# wzy_SCH1.net
KiCad netlist of a schematic drawn in Altium Designer
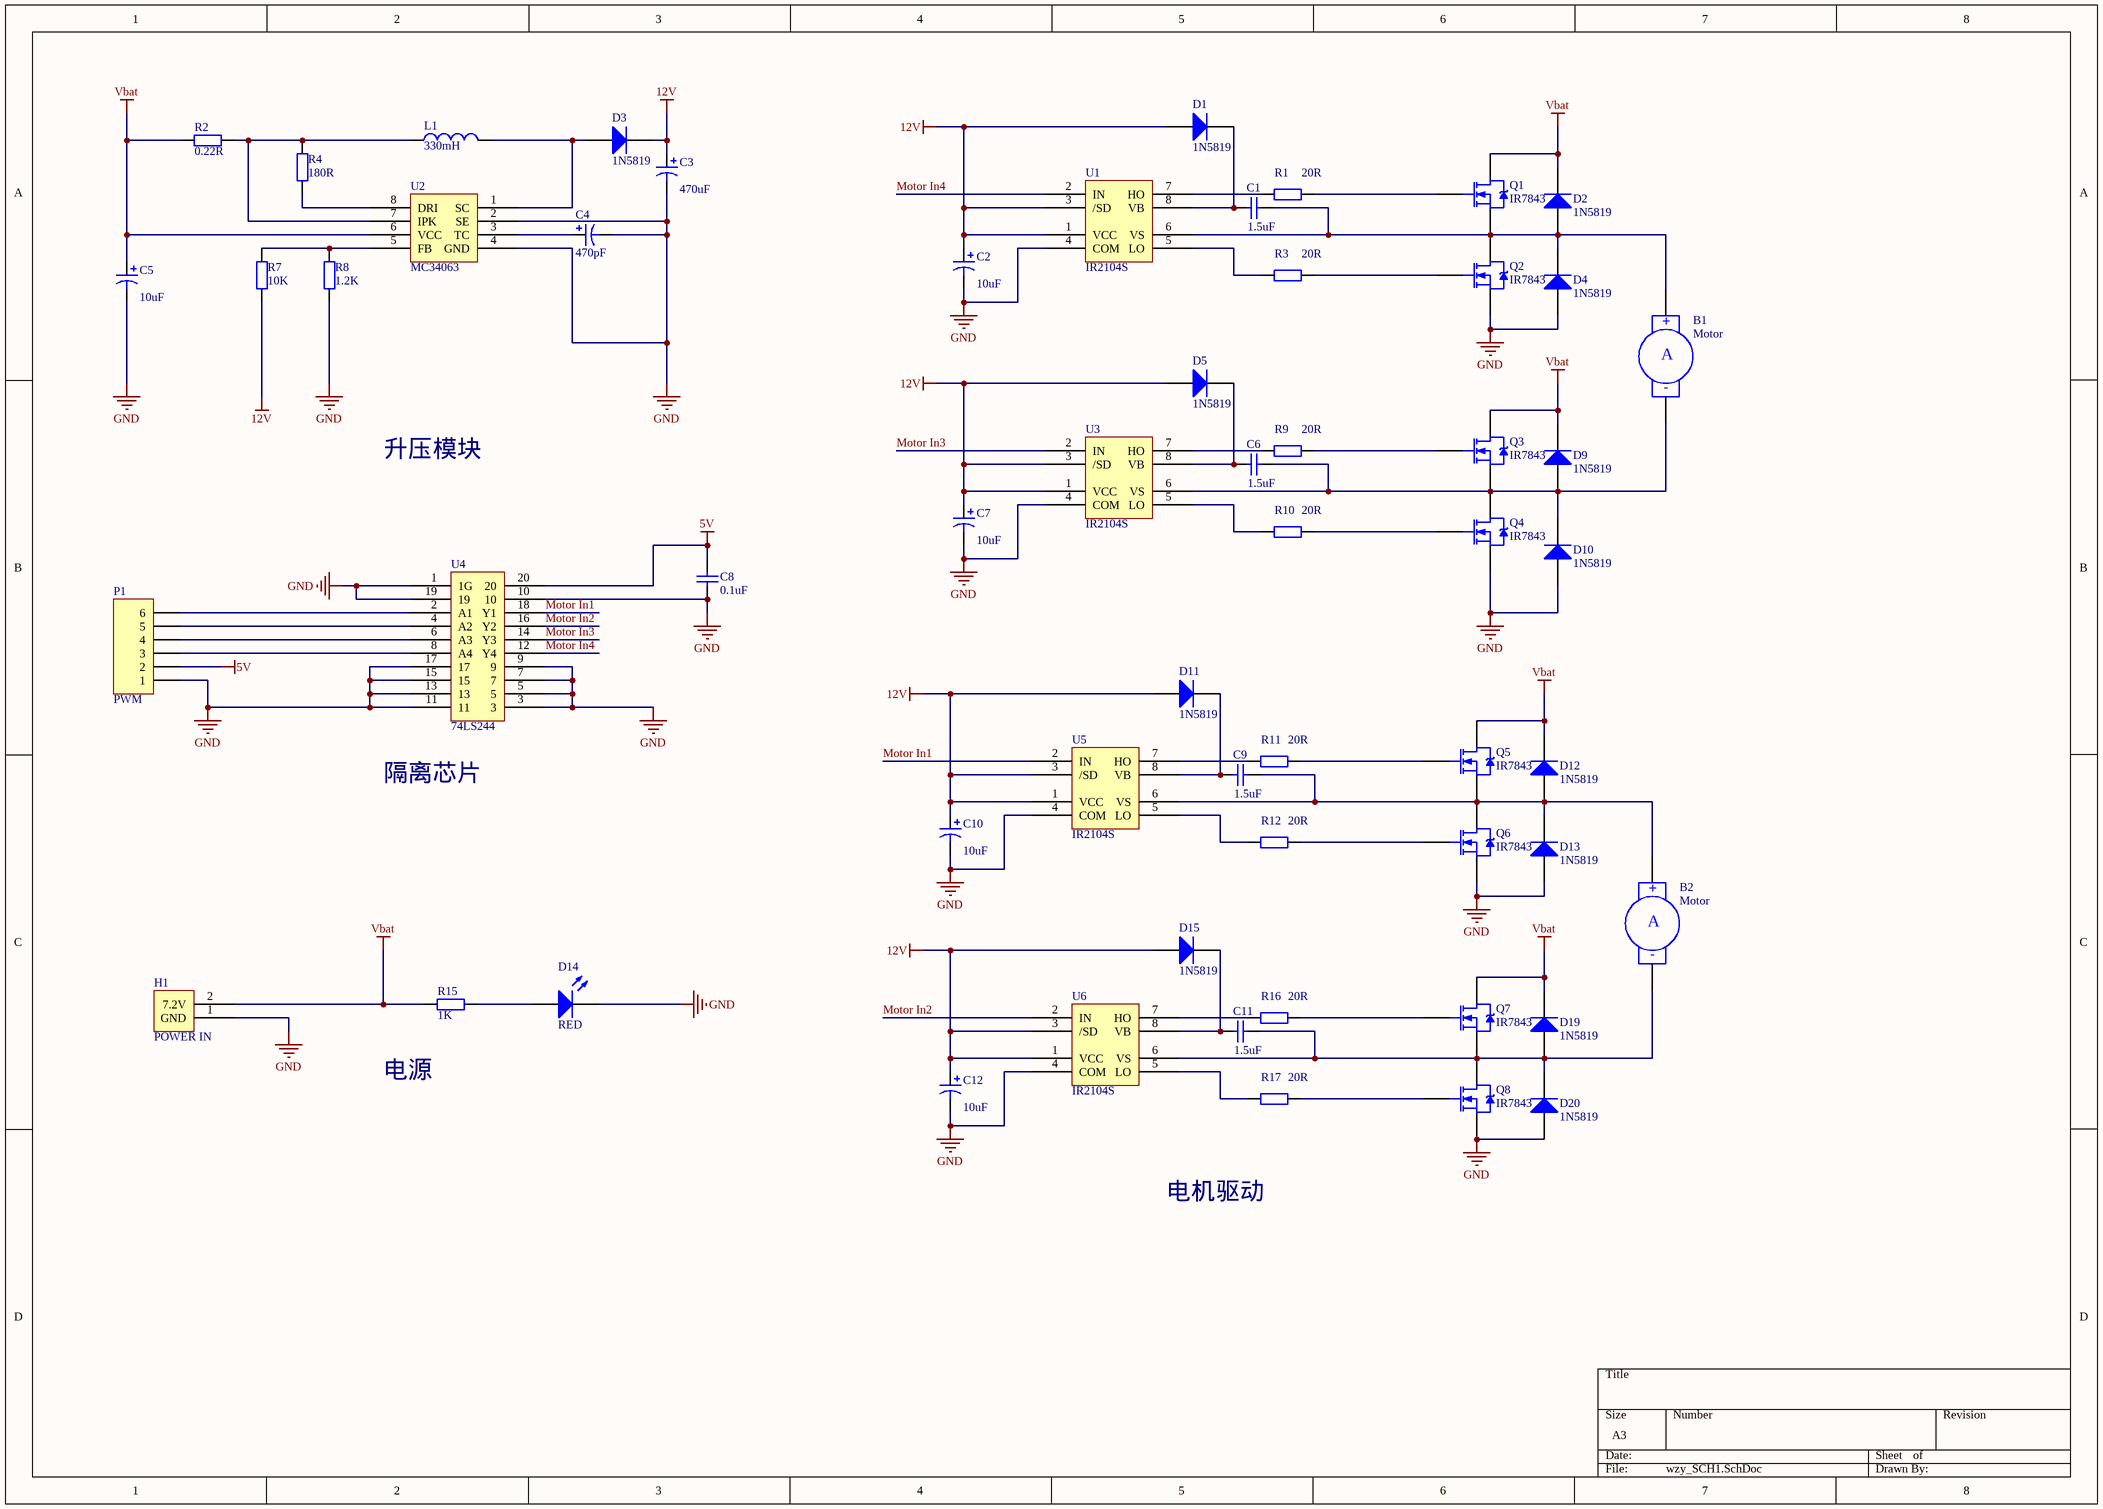
[diagram p0: wzy_SCH1.SchDoc]

(export (version "E")
  (design (tool "Eeschema 10.0.6"))
  (components
    (comp (ref "B1")
      (value "Motor")
      (footprint "KF301-2P")
      (description "Servo Motor")
      (fields (field (name "PUBLISHER") "Altium Limited"))
      (libsource (lib "Miscellaneous Devices") (part "Motor Servo"))
    )
    (comp (ref "B2")
      (value "Motor")
      (footprint "KF301-2P")
      (description "Servo Motor")
      (fields (field (name "PUBLISHER") "Altium Limited"))
      (libsource (lib "Miscellaneous Devices") (part "Motor Servo"))
    )
    (comp (ref "C1")
      (value "1.5uF")
      (footprint "0805(2012)")
      (description "Capacitor")
      (fields (field (name "Comment") "Cap") (field (name "PUBLISHER") "Altium Limited"))
      (libsource (lib "Miscellaneous Devices") (part "Cap"))
    )
    (comp (ref "C2")
      (value "10uF")
      (footprint "SOD-323(0805)")
      (description "Polarized Capacitor (Radial)")
      (fields (field (name "Comment") "Cap Pol1") (field (name "PUBLISHER") "Altium Limited"))
      (libsource (lib "Miscellaneous Devices") (part "Cap Pol1"))
    )
    (comp (ref "C3")
      (value "470uF")
      (footprint "RB5-10.5")
      (description "Polarized Capacitor (Radial)")
      (fields (field (name "Comment") "Cap Pol1") (field (name "PUBLISHER") "Altium Limited"))
      (libsource (lib "Miscellaneous Devices") (part "Cap Pol1"))
    )
    (comp (ref "C4")
      (value "470pF")
      (footprint "SOD-323(0805)")
      (description "Polarized Capacitor (Radial)")
      (fields (field (name "Comment") "Cap Pol1") (field (name "PUBLISHER") "Altium Limited"))
      (libsource (lib "Miscellaneous Devices") (part "Cap Pol1"))
    )
    (comp (ref "C5")
      (value "10uF")
      (footprint "SOD-323(0805)")
      (description "Polarized Capacitor (Radial)")
      (fields (field (name "Comment") "Cap Pol1") (field (name "PUBLISHER") "Altium Limited"))
      (libsource (lib "Miscellaneous Devices") (part "Cap Pol1"))
    )
    (comp (ref "C6")
      (value "1.5uF")
      (footprint "0805(2012)")
      (description "Capacitor")
      (fields (field (name "Comment") "Cap") (field (name "PUBLISHER") "Altium Limited"))
      (libsource (lib "Miscellaneous Devices") (part "Cap"))
    )
    (comp (ref "C7")
      (value "10uF")
      (footprint "SOD-323(0805)")
      (description "Polarized Capacitor (Radial)")
      (fields (field (name "Comment") "Cap Pol1") (field (name "PUBLISHER") "Altium Limited"))
      (libsource (lib "Miscellaneous Devices") (part "Cap Pol1"))
    )
    (comp (ref "C8")
      (value "0.1uF")
      (footprint "0805(2012)")
      (description "Capacitor")
      (fields (field (name "Comment") "Cap") (field (name "PUBLISHER") "Altium Limited"))
      (libsource (lib "LY") (part "Cap"))
    )
    (comp (ref "C9")
      (value "1.5uF")
      (footprint "0805(2012)")
      (description "Capacitor")
      (fields (field (name "Comment") "Cap") (field (name "PUBLISHER") "Altium Limited"))
      (libsource (lib "Miscellaneous Devices") (part "Cap"))
    )
    (comp (ref "C10")
      (value "10uF")
      (footprint "SOD-323(0805)")
      (description "Polarized Capacitor (Radial)")
      (fields (field (name "Comment") "Cap Pol1") (field (name "PUBLISHER") "Altium Limited"))
      (libsource (lib "Miscellaneous Devices") (part "Cap Pol1"))
    )
    (comp (ref "C11")
      (value "1.5uF")
      (footprint "0805(2012)")
      (description "Capacitor")
      (fields (field (name "Comment") "Cap") (field (name "PUBLISHER") "Altium Limited"))
      (libsource (lib "Miscellaneous Devices") (part "Cap"))
    )
    (comp (ref "C12")
      (value "10uF")
      (footprint "SOD-323(0805)")
      (description "Polarized Capacitor (Radial)")
      (fields (field (name "Comment") "Cap Pol1") (field (name "PUBLISHER") "Altium Limited"))
      (libsource (lib "Miscellaneous Devices") (part "Cap Pol1"))
    )
    (comp (ref "D1")
      (value "1N5819")
      (footprint "0805(2012)")
      (description "Silicon Epitaxial Planar Diode for Various Detector, Modulator, Demodulator")
      (fields (field (name "PUBLISHER") "Altium Limited"))
      (libsource (lib "Renesas Diode") (part "1N4148"))
    )
    (comp (ref "D2")
      (value "1N5819")
      (footprint "0805(2012)")
      (description "Silicon Epitaxial Planar Diode for Various Detector, Modulator, Demodulator")
      (fields (field (name "PUBLISHER") "Altium Limited"))
      (libsource (lib "Renesas Diode") (part "1N4148"))
    )
    (comp (ref "D3")
      (value "1N5819")
      (footprint "0805(2012)")
      (description "Silicon Epitaxial Planar Diode for Various Detector, Modulator, Demodulator")
      (fields (field (name "PUBLISHER") "Altium Limited"))
      (libsource (lib "Renesas Diode") (part "1N4148"))
    )
    (comp (ref "D4")
      (value "1N5819")
      (footprint "0805(2012)")
      (description "Silicon Epitaxial Planar Diode for Various Detector, Modulator, Demodulator")
      (fields (field (name "PUBLISHER") "Altium Limited"))
      (libsource (lib "Renesas Diode") (part "1N4148"))
    )
    (comp (ref "D5")
      (value "1N5819")
      (footprint "0805(2012)")
      (description "Silicon Epitaxial Planar Diode for Various Detector, Modulator, Demodulator")
      (fields (field (name "PUBLISHER") "Altium Limited"))
      (libsource (lib "Renesas Diode") (part "1N4148"))
    )
    (comp (ref "D9")
      (value "1N5819")
      (footprint "0805(2012)")
      (description "Silicon Epitaxial Planar Diode for Various Detector, Modulator, Demodulator")
      (fields (field (name "PUBLISHER") "Altium Limited"))
      (libsource (lib "Renesas Diode") (part "1N4148"))
    )
    (comp (ref "D10")
      (value "1N5819")
      (footprint "0805(2012)")
      (description "Silicon Epitaxial Planar Diode for Various Detector, Modulator, Demodulator")
      (fields (field (name "PUBLISHER") "Altium Limited"))
      (libsource (lib "Renesas Diode") (part "1N4148"))
    )
    (comp (ref "D11")
      (value "1N5819")
      (footprint "0805(2012)")
      (description "Silicon Epitaxial Planar Diode for Various Detector, Modulator, Demodulator")
      (fields (field (name "PUBLISHER") "Altium Limited"))
      (libsource (lib "Renesas Diode") (part "1N4148"))
    )
    (comp (ref "D12")
      (value "1N5819")
      (footprint "0805(2012)")
      (description "Silicon Epitaxial Planar Diode for Various Detector, Modulator, Demodulator")
      (fields (field (name "PUBLISHER") "Altium Limited"))
      (libsource (lib "Renesas Diode") (part "1N4148"))
    )
    (comp (ref "D13")
      (value "1N5819")
      (footprint "0805(2012)")
      (description "Silicon Epitaxial Planar Diode for Various Detector, Modulator, Demodulator")
      (fields (field (name "PUBLISHER") "Altium Limited"))
      (libsource (lib "Renesas Diode") (part "1N4148"))
    )
    (comp (ref "D14")
      (value "RED")
      (footprint "0805LED")
      (description "Typical RED, GREEN, YELLOW, AMBER GaAs LED")
      (fields (field (name "PUBLISHER") "Altium Limited"))
      (libsource (lib "LY") (part "LED2"))
    )
    (comp (ref "D15")
      (value "1N5819")
      (footprint "0805(2012)")
      (description "Silicon Epitaxial Planar Diode for Various Detector, Modulator, Demodulator")
      (fields (field (name "PUBLISHER") "Altium Limited"))
      (libsource (lib "Renesas Diode") (part "1N4148"))
    )
    (comp (ref "D19")
      (value "1N5819")
      (footprint "0805(2012)")
      (description "Silicon Epitaxial Planar Diode for Various Detector, Modulator, Demodulator")
      (fields (field (name "PUBLISHER") "Altium Limited"))
      (libsource (lib "Renesas Diode") (part "1N4148"))
    )
    (comp (ref "D20")
      (value "1N5819")
      (footprint "0805(2012)")
      (description "Silicon Epitaxial Planar Diode for Various Detector, Modulator, Demodulator")
      (fields (field (name "PUBLISHER") "Altium Limited"))
      (libsource (lib "Renesas Diode") (part "1N4148"))
    )
    (comp (ref "H1")
      (value "POWER IN")
      (footprint "KF301-2P")
      (libsource (lib "MOS motor") (part "POWER IN"))
    )
    (comp (ref "L1")
      (value "330mH")
      (footprint "电感10*12")
      (description "Inductor")
      (fields (field (name "PUBLISHER") "Altium Limited"))
      (libsource (lib "Miscellaneous Devices") (part "Inductor"))
    )
    (comp (ref "P1")
      (value "PWM")
      (footprint "HDR1X6")
      (description "Header, 6-Pin")
      (fields (field (name "PUBLISHER") "Altium Limited"))
      (libsource (lib "Miscellaneous Connectors") (part "Header 6"))
    )
    (comp (ref "Q1")
      (value "IR7843")
      (footprint "LR7843")
      (description "N-Channel Power MOSFET")
      (fields (field (name "PUBLISHER") "Altium Limited"))
      (libsource (lib "PowerIn") (part "IR7843"))
    )
    (comp (ref "Q2")
      (value "IR7843")
      (footprint "LR7843")
      (description "N-Channel Power MOSFET")
      (fields (field (name "PUBLISHER") "Altium Limited"))
      (libsource (lib "PowerIn") (part "IR7843"))
    )
    (comp (ref "Q3")
      (value "IR7843")
      (footprint "LR7843")
      (description "N-Channel Power MOSFET")
      (fields (field (name "PUBLISHER") "Altium Limited"))
      (libsource (lib "PowerIn") (part "IR7843"))
    )
    (comp (ref "Q4")
      (value "IR7843")
      (footprint "LR7843")
      (description "N-Channel Power MOSFET")
      (fields (field (name "PUBLISHER") "Altium Limited"))
      (libsource (lib "PowerIn") (part "IR7843"))
    )
    (comp (ref "Q5")
      (value "IR7843")
      (footprint "LR7843")
      (description "N-Channel Power MOSFET")
      (fields (field (name "PUBLISHER") "Altium Limited"))
      (libsource (lib "PowerIn") (part "IR7843"))
    )
    (comp (ref "Q6")
      (value "IR7843")
      (footprint "LR7843")
      (description "N-Channel Power MOSFET")
      (fields (field (name "PUBLISHER") "Altium Limited"))
      (libsource (lib "PowerIn") (part "IR7843"))
    )
    (comp (ref "Q7")
      (value "IR7843")
      (footprint "LR7843")
      (description "N-Channel Power MOSFET")
      (fields (field (name "PUBLISHER") "Altium Limited"))
      (libsource (lib "PowerIn") (part "IR7843"))
    )
    (comp (ref "Q8")
      (value "IR7843")
      (footprint "LR7843")
      (description "N-Channel Power MOSFET")
      (fields (field (name "PUBLISHER") "Altium Limited"))
      (libsource (lib "PowerIn") (part "IR7843"))
    )
    (comp (ref "R1")
      (value "20R")
      (footprint "0805(2012)")
      (description "Resistor")
      (fields (field (name "Comment") "Res2") (field (name "PUBLISHER") "Altium Limited"))
      (libsource (lib "altium-import") (part "root_0_Res2_"))
    )
    (comp (ref "R2")
      (value "0.22R")
      (footprint "1206(3216)")
      (description "Resistor")
      (fields (field (name "Comment") "Res2") (field (name "PUBLISHER") "Altium Limited"))
      (libsource (lib "altium-import") (part "root_2_Res2_"))
    )
    (comp (ref "R3")
      (value "20R")
      (footprint "0805(2012)")
      (description "Resistor")
      (fields (field (name "Comment") "Res2") (field (name "PUBLISHER") "Altium Limited"))
      (libsource (lib "altium-import") (part "root_0_Res2_"))
    )
    (comp (ref "R4")
      (value "180R")
      (footprint "0805(2012)")
      (description "Resistor")
      (fields (field (name "Comment") "Res2") (field (name "PUBLISHER") "Altium Limited"))
      (libsource (lib "LY") (part "Res2"))
    )
    (comp (ref "R7")
      (value "10K")
      (footprint "0805(2012)")
      (description "Resistor")
      (fields (field (name "Comment") "Res2") (field (name "PUBLISHER") "Altium Limited"))
      (libsource (lib "LY") (part "Res2"))
    )
    (comp (ref "R8")
      (value "1.2K")
      (footprint "0805(2012)")
      (description "Resistor")
      (fields (field (name "Comment") "Res2") (field (name "PUBLISHER") "Altium Limited"))
      (libsource (lib "LY") (part "Res2"))
    )
    (comp (ref "R9")
      (value "20R")
      (footprint "0805(2012)")
      (description "Resistor")
      (fields (field (name "Comment") "Res2") (field (name "PUBLISHER") "Altium Limited"))
      (libsource (lib "altium-import") (part "root_0_Res2_"))
    )
    (comp (ref "R10")
      (value "20R")
      (footprint "0805(2012)")
      (description "Resistor")
      (fields (field (name "Comment") "Res2") (field (name "PUBLISHER") "Altium Limited"))
      (libsource (lib "altium-import") (part "root_0_Res2_"))
    )
    (comp (ref "R11")
      (value "20R")
      (footprint "0805(2012)")
      (description "Resistor")
      (fields (field (name "Comment") "Res2") (field (name "PUBLISHER") "Altium Limited"))
      (libsource (lib "altium-import") (part "root_0_Res2_"))
    )
    (comp (ref "R12")
      (value "20R")
      (footprint "0805(2012)")
      (description "Resistor")
      (fields (field (name "Comment") "Res2") (field (name "PUBLISHER") "Altium Limited"))
      (libsource (lib "altium-import") (part "root_0_Res2_"))
    )
    (comp (ref "R15")
      (value "1K")
      (footprint "0805(2012)")
      (description "Resistor")
      (fields (field (name "Comment") "Res2") (field (name "PUBLISHER") "Altium Limited"))
      (libsource (lib "") (part "Res2_1"))
    )
    (comp (ref "R16")
      (value "20R")
      (footprint "0805(2012)")
      (description "Resistor")
      (fields (field (name "Comment") "Res2") (field (name "PUBLISHER") "Altium Limited"))
      (libsource (lib "altium-import") (part "root_0_Res2_"))
    )
    (comp (ref "R17")
      (value "20R")
      (footprint "0805(2012)")
      (description "Resistor")
      (fields (field (name "Comment") "Res2") (field (name "PUBLISHER") "Altium Limited"))
      (libsource (lib "altium-import") (part "root_0_Res2_"))
    )
    (comp (ref "U1") (value "IR2104S") (footprint "IR2104S") (libsource (lib "LY") (part "IR2104S")))
    (comp (ref "U2") (value "MC34063") (footprint "MC34063") (libsource (lib "LY") (part "MC34063")))
    (comp (ref "U3") (value "IR2104S") (footprint "IR2104S") (libsource (lib "LY") (part "IR2104S")))
    (comp (ref "U4") (value "74LS244") (footprint "74ls244DA") (libsource (lib "LY") (part "74LS244")))
    (comp (ref "U5") (value "IR2104S") (footprint "IR2104S") (libsource (lib "LY") (part "IR2104S")))
    (comp (ref "U6") (value "IR2104S") (footprint "IR2104S") (libsource (lib "LY") (part "IR2104S")))
  )
  (nets
    (net (code "1") (name "/Motor In1") (class "Default")
      (node (ref "U4") (pin "18") (pinfunction "Y1_18") (pintype "passive"))
      (node (ref "U5") (pin "2") (pinfunction "IN_2") (pintype "passive"))
    )
    (net (code "2") (name "/Motor In2") (class "Default")
      (node (ref "U4") (pin "16") (pinfunction "Y2_16") (pintype "passive"))
      (node (ref "U6") (pin "2") (pinfunction "IN_2") (pintype "passive"))
    )
    (net (code "3") (name "/Motor In3") (class "Default")
      (node (ref "U3") (pin "2") (pinfunction "IN_2") (pintype "passive"))
      (node (ref "U4") (pin "14") (pinfunction "Y3_14") (pintype "passive"))
    )
    (net (code "4") (name "/Motor In4") (class "Default")
      (node (ref "U1") (pin "2") (pinfunction "IN_2") (pintype "passive"))
      (node (ref "U4") (pin "12") (pinfunction "Y4_12") (pintype "passive"))
    )
    (net (code "5") (name "5V") (class "Default")
      (node (ref "C8") (pin "2") (pinfunction "2_2") (pintype "passive"))
      (node (ref "P1") (pin "2") (pinfunction "2_2") (pintype "passive"))
      (node (ref "U4") (pin "20") (pinfunction "20_20") (pintype "passive"))
    )
    (net (code "6") (name "12V") (class "Default")
      (node (ref "C10") (pin "1") (pinfunction "1_1") (pintype "passive"))
      (node (ref "C12") (pin "1") (pinfunction "1_1") (pintype "passive"))
      (node (ref "C2") (pin "1") (pinfunction "1_1") (pintype "passive"))
      (node (ref "C3") (pin "1") (pinfunction "1_1") (pintype "passive"))
      (node (ref "C7") (pin "1") (pinfunction "1_1") (pintype "passive"))
      (node (ref "D1") (pin "2") (pinfunction "A_2") (pintype "passive"))
      (node (ref "D11") (pin "2") (pinfunction "A_2") (pintype "passive"))
      (node (ref "D15") (pin "2") (pinfunction "A_2") (pintype "passive"))
      (node (ref "D3") (pin "1") (pinfunction "K_1") (pintype "passive"))
      (node (ref "D5") (pin "2") (pinfunction "A_2") (pintype "passive"))
      (node (ref "R7") (pin "1") (pinfunction "1_1") (pintype "passive"))
      (node (ref "U1") (pin "1") (pinfunction "VCC_1") (pintype "passive"))
      (node (ref "U1") (pin "3") (pinfunction "/SD_3") (pintype "passive"))
      (node (ref "U3") (pin "1") (pinfunction "VCC_1") (pintype "passive"))
      (node (ref "U3") (pin "3") (pinfunction "/SD_3") (pintype "passive"))
      (node (ref "U5") (pin "1") (pinfunction "VCC_1") (pintype "passive"))
      (node (ref "U5") (pin "3") (pinfunction "/SD_3") (pintype "passive"))
      (node (ref "U6") (pin "1") (pinfunction "VCC_1") (pintype "passive"))
      (node (ref "U6") (pin "3") (pinfunction "/SD_3") (pintype "passive"))
    )
    (net (code "7") (name "GND") (class "Default")
      (node (ref "C10") (pin "2") (pinfunction "2_2") (pintype "passive"))
      (node (ref "C12") (pin "2") (pinfunction "2_2") (pintype "passive"))
      (node (ref "C2") (pin "2") (pinfunction "2_2") (pintype "passive"))
      (node (ref "C3") (pin "2") (pinfunction "2_2") (pintype "passive"))
      (node (ref "C4") (pin "2") (pinfunction "2_2") (pintype "passive"))
      (node (ref "C5") (pin "2") (pinfunction "2_2") (pintype "passive"))
      (node (ref "C7") (pin "2") (pinfunction "2_2") (pintype "passive"))
      (node (ref "C8") (pin "1") (pinfunction "1_1") (pintype "passive"))
      (node (ref "D10") (pin "2") (pinfunction "A_2") (pintype "passive"))
      (node (ref "D13") (pin "2") (pinfunction "A_2") (pintype "passive"))
      (node (ref "D14") (pin "2") (pinfunction "K_2") (pintype "passive"))
      (node (ref "D20") (pin "2") (pinfunction "A_2") (pintype "passive"))
      (node (ref "D4") (pin "2") (pinfunction "A_2") (pintype "passive"))
      (node (ref "H1") (pin "1") (pinfunction "GND_1") (pintype "passive"))
      (node (ref "P1") (pin "1") (pinfunction "1_1") (pintype "passive"))
      (node (ref "Q2") (pin "3") (pinfunction "S_3") (pintype "passive"))
      (node (ref "Q4") (pin "3") (pinfunction "S_3") (pintype "passive"))
      (node (ref "Q6") (pin "3") (pinfunction "S_3") (pintype "passive"))
      (node (ref "Q8") (pin "3") (pinfunction "S_3") (pintype "passive"))
      (node (ref "R8") (pin "1") (pinfunction "1_1") (pintype "passive"))
      (node (ref "U1") (pin "4") (pinfunction "COM_4") (pintype "passive"))
      (node (ref "U2") (pin "2") (pinfunction "SE_2") (pintype "passive"))
      (node (ref "U2") (pin "4") (pinfunction "GND_4") (pintype "passive"))
      (node (ref "U3") (pin "4") (pinfunction "COM_4") (pintype "passive"))
      (node (ref "U4") (pin "1") (pinfunction "1G_1") (pintype "passive"))
      (node (ref "U4") (pin "10") (pinfunction "10_10") (pintype "passive"))
      (node (ref "U4") (pin "11") (pinfunction "11_11") (pintype "passive"))
      (node (ref "U4") (pin "13") (pinfunction "13_13") (pintype "passive"))
      (node (ref "U4") (pin "15") (pinfunction "15_15") (pintype "passive"))
      (node (ref "U4") (pin "17") (pinfunction "17_17") (pintype "passive"))
      (node (ref "U4") (pin "19") (pinfunction "19_19") (pintype "passive"))
      (node (ref "U4") (pin "3") (pinfunction "3_3") (pintype "passive"))
      (node (ref "U4") (pin "5") (pinfunction "5_5") (pintype "passive"))
      (node (ref "U4") (pin "7") (pinfunction "7_7") (pintype "passive"))
      (node (ref "U4") (pin "9") (pinfunction "9_9") (pintype "passive"))
      (node (ref "U5") (pin "4") (pinfunction "COM_4") (pintype "passive"))
      (node (ref "U6") (pin "4") (pinfunction "COM_4") (pintype "passive"))
    )
    (net (code "8") (name "Net-(B1-+)") (class "Default")
      (node (ref "B1") (pin "1") (pinfunction "+_1") (pintype "passive"))
      (node (ref "C1") (pin "2") (pinfunction "2_2") (pintype "passive"))
      (node (ref "D2") (pin "2") (pinfunction "A_2") (pintype "passive"))
      (node (ref "D4") (pin "1") (pinfunction "K_1") (pintype "passive"))
      (node (ref "Q1") (pin "3") (pinfunction "S_3") (pintype "passive"))
      (node (ref "Q2") (pin "2") (pinfunction "D_2") (pintype "passive"))
      (node (ref "U1") (pin "6") (pinfunction "VS_6") (pintype "passive"))
    )
    (net (code "9") (name "Net-(B1--)") (class "Default")
      (node (ref "B1") (pin "2") (pinfunction "-_2") (pintype "passive"))
      (node (ref "C6") (pin "2") (pinfunction "2_2") (pintype "passive"))
      (node (ref "D10") (pin "1") (pinfunction "K_1") (pintype "passive"))
      (node (ref "D9") (pin "2") (pinfunction "A_2") (pintype "passive"))
      (node (ref "Q3") (pin "3") (pinfunction "S_3") (pintype "passive"))
      (node (ref "Q4") (pin "2") (pinfunction "D_2") (pintype "passive"))
      (node (ref "U3") (pin "6") (pinfunction "VS_6") (pintype "passive"))
    )
    (net (code "10") (name "Net-(B2-+)") (class "Default")
      (node (ref "B2") (pin "1") (pinfunction "+_1") (pintype "passive"))
      (node (ref "C9") (pin "2") (pinfunction "2_2") (pintype "passive"))
      (node (ref "D12") (pin "2") (pinfunction "A_2") (pintype "passive"))
      (node (ref "D13") (pin "1") (pinfunction "K_1") (pintype "passive"))
      (node (ref "Q5") (pin "3") (pinfunction "S_3") (pintype "passive"))
      (node (ref "Q6") (pin "2") (pinfunction "D_2") (pintype "passive"))
      (node (ref "U5") (pin "6") (pinfunction "VS_6") (pintype "passive"))
    )
    (net (code "11") (name "Net-(B2--)") (class "Default")
      (node (ref "B2") (pin "2") (pinfunction "-_2") (pintype "passive"))
      (node (ref "C11") (pin "2") (pinfunction "2_2") (pintype "passive"))
      (node (ref "D19") (pin "2") (pinfunction "A_2") (pintype "passive"))
      (node (ref "D20") (pin "1") (pinfunction "K_1") (pintype "passive"))
      (node (ref "Q7") (pin "3") (pinfunction "S_3") (pintype "passive"))
      (node (ref "Q8") (pin "2") (pinfunction "D_2") (pintype "passive"))
      (node (ref "U6") (pin "6") (pinfunction "VS_6") (pintype "passive"))
    )
    (net (code "12") (name "Net-(D1-K)") (class "Default")
      (node (ref "C1") (pin "1") (pinfunction "1_1") (pintype "passive"))
      (node (ref "D1") (pin "1") (pinfunction "K_1") (pintype "passive"))
      (node (ref "U1") (pin "8") (pinfunction "VB_8") (pintype "passive"))
    )
    (net (code "13") (name "Net-(D3-A)") (class "Default")
      (node (ref "D3") (pin "2") (pinfunction "A_2") (pintype "passive"))
      (node (ref "L1") (pin "2") (pinfunction "2_2") (pintype "passive"))
      (node (ref "U2") (pin "1") (pinfunction "SC_1") (pintype "passive"))
    )
    (net (code "14") (name "Net-(D5-K)") (class "Default")
      (node (ref "C6") (pin "1") (pinfunction "1_1") (pintype "passive"))
      (node (ref "D5") (pin "1") (pinfunction "K_1") (pintype "passive"))
      (node (ref "U3") (pin "8") (pinfunction "VB_8") (pintype "passive"))
    )
    (net (code "15") (name "Net-(D11-K)") (class "Default")
      (node (ref "C9") (pin "1") (pinfunction "1_1") (pintype "passive"))
      (node (ref "D11") (pin "1") (pinfunction "K_1") (pintype "passive"))
      (node (ref "U5") (pin "8") (pinfunction "VB_8") (pintype "passive"))
    )
    (net (code "16") (name "Net-(D14-A)") (class "Default")
      (node (ref "D14") (pin "1") (pinfunction "A_1") (pintype "passive"))
      (node (ref "R15") (pin "2") (pinfunction "2_2") (pintype "passive"))
    )
    (net (code "17") (name "Net-(D15-K)") (class "Default")
      (node (ref "C11") (pin "1") (pinfunction "1_1") (pintype "passive"))
      (node (ref "D15") (pin "1") (pinfunction "K_1") (pintype "passive"))
      (node (ref "U6") (pin "8") (pinfunction "VB_8") (pintype "passive"))
    )
    (net (code "18") (name "Net-(Q1-G)") (class "Default")
      (node (ref "Q1") (pin "1") (pinfunction "G_1") (pintype "passive"))
      (node (ref "R1") (pin "2") (pinfunction "2_2") (pintype "passive"))
    )
    (net (code "19") (name "Net-(Q2-G)") (class "Default")
      (node (ref "Q2") (pin "1") (pinfunction "G_1") (pintype "passive"))
      (node (ref "R3") (pin "2") (pinfunction "2_2") (pintype "passive"))
    )
    (net (code "20") (name "Net-(Q3-G)") (class "Default")
      (node (ref "Q3") (pin "1") (pinfunction "G_1") (pintype "passive"))
      (node (ref "R9") (pin "2") (pinfunction "2_2") (pintype "passive"))
    )
    (net (code "21") (name "Net-(Q4-G)") (class "Default")
      (node (ref "Q4") (pin "1") (pinfunction "G_1") (pintype "passive"))
      (node (ref "R10") (pin "2") (pinfunction "2_2") (pintype "passive"))
    )
    (net (code "22") (name "Net-(Q5-G)") (class "Default")
      (node (ref "Q5") (pin "1") (pinfunction "G_1") (pintype "passive"))
      (node (ref "R11") (pin "2") (pinfunction "2_2") (pintype "passive"))
    )
    (net (code "23") (name "Net-(Q6-G)") (class "Default")
      (node (ref "Q6") (pin "1") (pinfunction "G_1") (pintype "passive"))
      (node (ref "R12") (pin "2") (pinfunction "2_2") (pintype "passive"))
    )
    (net (code "24") (name "Net-(Q7-G)") (class "Default")
      (node (ref "Q7") (pin "1") (pinfunction "G_1") (pintype "passive"))
      (node (ref "R16") (pin "2") (pinfunction "2_2") (pintype "passive"))
    )
    (net (code "25") (name "Net-(Q8-G)") (class "Default")
      (node (ref "Q8") (pin "1") (pinfunction "G_1") (pintype "passive"))
      (node (ref "R17") (pin "2") (pinfunction "2_2") (pintype "passive"))
    )
    (net (code "26") (name "Net-(U1-HO)") (class "Default")
      (node (ref "R1") (pin "1") (pinfunction "1_1") (pintype "passive"))
      (node (ref "U1") (pin "7") (pinfunction "HO_7") (pintype "passive"))
    )
    (net (code "27") (name "Net-(U1-LO)") (class "Default")
      (node (ref "R3") (pin "1") (pinfunction "1_1") (pintype "passive"))
      (node (ref "U1") (pin "5") (pinfunction "LO_5") (pintype "passive"))
    )
    (net (code "28") (name "Net-(U2-DRI)") (class "Default")
      (node (ref "R4") (pin "1") (pinfunction "1_1") (pintype "passive"))
      (node (ref "U2") (pin "8") (pinfunction "DRI_8") (pintype "passive"))
    )
    (net (code "29") (name "Net-(U2-FB)") (class "Default")
      (node (ref "R7") (pin "2") (pinfunction "2_2") (pintype "passive"))
      (node (ref "R8") (pin "2") (pinfunction "2_2") (pintype "passive"))
      (node (ref "U2") (pin "5") (pinfunction "FB_5") (pintype "passive"))
    )
    (net (code "30") (name "Net-(U2-IPK)") (class "Default")
      (node (ref "L1") (pin "1") (pinfunction "1_1") (pintype "passive"))
      (node (ref "R2") (pin "1") (pinfunction "1_1") (pintype "passive"))
      (node (ref "R4") (pin "2") (pinfunction "2_2") (pintype "passive"))
      (node (ref "U2") (pin "7") (pinfunction "IPK_7") (pintype "passive"))
    )
    (net (code "31") (name "Net-(U2-TC)") (class "Default")
      (node (ref "C4") (pin "1") (pinfunction "1_1") (pintype "passive"))
      (node (ref "U2") (pin "3") (pinfunction "TC_3") (pintype "passive"))
    )
    (net (code "32") (name "Net-(U3-HO)") (class "Default")
      (node (ref "R9") (pin "1") (pinfunction "1_1") (pintype "passive"))
      (node (ref "U3") (pin "7") (pinfunction "HO_7") (pintype "passive"))
    )
    (net (code "33") (name "Net-(U3-LO)") (class "Default")
      (node (ref "R10") (pin "1") (pinfunction "1_1") (pintype "passive"))
      (node (ref "U3") (pin "5") (pinfunction "LO_5") (pintype "passive"))
    )
    (net (code "34") (name "Net-(U4-A1)") (class "Default")
      (node (ref "P1") (pin "6") (pinfunction "6_6") (pintype "passive"))
      (node (ref "U4") (pin "2") (pinfunction "A1_2") (pintype "passive"))
    )
    (net (code "35") (name "Net-(U4-A2)") (class "Default")
      (node (ref "P1") (pin "5") (pinfunction "5_5") (pintype "passive"))
      (node (ref "U4") (pin "4") (pinfunction "A2_4") (pintype "passive"))
    )
    (net (code "36") (name "Net-(U4-A3)") (class "Default")
      (node (ref "P1") (pin "4") (pinfunction "4_4") (pintype "passive"))
      (node (ref "U4") (pin "6") (pinfunction "A3_6") (pintype "passive"))
    )
    (net (code "37") (name "Net-(U4-A4)") (class "Default")
      (node (ref "P1") (pin "3") (pinfunction "3_3") (pintype "passive"))
      (node (ref "U4") (pin "8") (pinfunction "A4_8") (pintype "passive"))
    )
    (net (code "38") (name "Net-(U5-HO)") (class "Default")
      (node (ref "R11") (pin "1") (pinfunction "1_1") (pintype "passive"))
      (node (ref "U5") (pin "7") (pinfunction "HO_7") (pintype "passive"))
    )
    (net (code "39") (name "Net-(U5-LO)") (class "Default")
      (node (ref "R12") (pin "1") (pinfunction "1_1") (pintype "passive"))
      (node (ref "U5") (pin "5") (pinfunction "LO_5") (pintype "passive"))
    )
    (net (code "40") (name "Net-(U6-HO)") (class "Default")
      (node (ref "R16") (pin "1") (pinfunction "1_1") (pintype "passive"))
      (node (ref "U6") (pin "7") (pinfunction "HO_7") (pintype "passive"))
    )
    (net (code "41") (name "Net-(U6-LO)") (class "Default")
      (node (ref "R17") (pin "1") (pinfunction "1_1") (pintype "passive"))
      (node (ref "U6") (pin "5") (pinfunction "LO_5") (pintype "passive"))
    )
    (net (code "42") (name "Vbat") (class "Default")
      (node (ref "C5") (pin "1") (pinfunction "1_1") (pintype "passive"))
      (node (ref "D12") (pin "1") (pinfunction "K_1") (pintype "passive"))
      (node (ref "D19") (pin "1") (pinfunction "K_1") (pintype "passive"))
      (node (ref "D2") (pin "1") (pinfunction "K_1") (pintype "passive"))
      (node (ref "D9") (pin "1") (pinfunction "K_1") (pintype "passive"))
      (node (ref "H1") (pin "2") (pinfunction "7.2V_2") (pintype "passive"))
      (node (ref "Q1") (pin "2") (pinfunction "D_2") (pintype "passive"))
      (node (ref "Q3") (pin "2") (pinfunction "D_2") (pintype "passive"))
      (node (ref "Q5") (pin "2") (pinfunction "D_2") (pintype "passive"))
      (node (ref "Q7") (pin "2") (pinfunction "D_2") (pintype "passive"))
      (node (ref "R15") (pin "1") (pinfunction "1_1") (pintype "passive"))
      (node (ref "R2") (pin "2") (pinfunction "2_2") (pintype "passive"))
      (node (ref "U2") (pin "6") (pinfunction "VCC_6") (pintype "passive"))
    )
  )
)
